# trackduino_mini.net
KiCad netlist of a schematic drawn in EAGLE
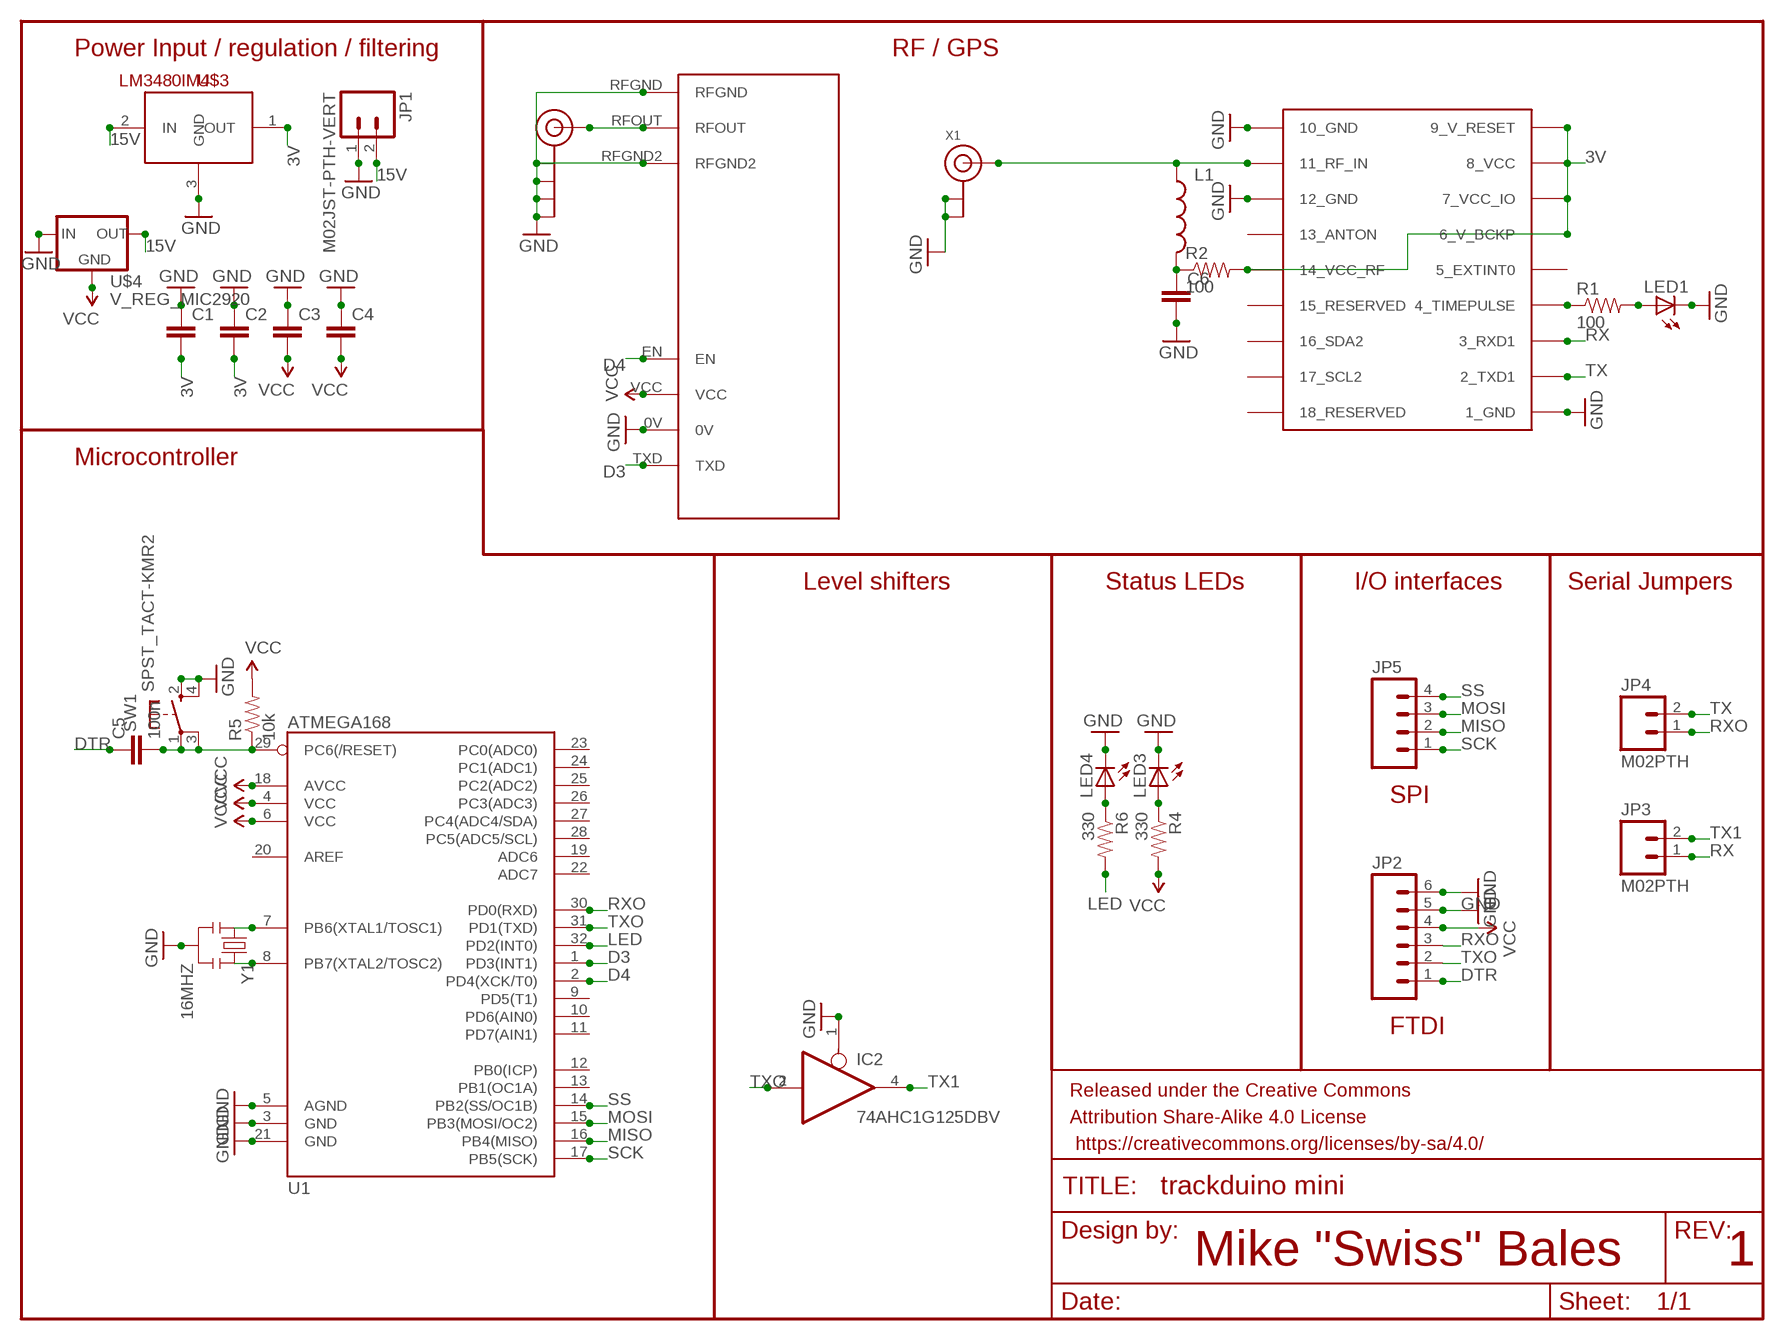
[diagram p0: schematic, sheet 1]

(export (version "E")
  (design (tool "Eeschema 10.0.6"))
  (components
    (comp (ref "C1")
      (value "CAP0805")
      (footprint "eagle-import:0805")
      (libsource (lib "eagle-import") (part "CAP0805"))
    )
    (comp (ref "C2")
      (value "CAP0805")
      (footprint "eagle-import:0805")
      (libsource (lib "eagle-import") (part "CAP0805"))
    )
    (comp (ref "C3")
      (value "CAP0805")
      (footprint "eagle-import:0805")
      (libsource (lib "eagle-import") (part "CAP0805"))
    )
    (comp (ref "C4")
      (value "CAP0805")
      (footprint "eagle-import:0805")
      (libsource (lib "eagle-import") (part "CAP0805"))
    )
    (comp (ref "C5")
      (value "100n")
      (footprint "eagle-import:0805")
      (libsource (lib "eagle-import") (part "CAP0805"))
    )
    (comp (ref "C6")
      (value "CAP0805")
      (footprint "eagle-import:0805")
      (libsource (lib "eagle-import") (part "CAP0805"))
    )
    (comp (ref "FRAME1")
      (value "FRAME-LETTER")
      (footprint "eagle-import:CREATIVE_COMMONS")
      (libsource (lib "eagle-import") (part "FRAME-LETTER"))
    )
    (comp (ref "IC2")
      (value "74AHC1G125DBV")
      (footprint "eagle-import:SOT23-5")
      (libsource (lib "eagle-import") (part "741G125DBVAHC"))
    )
    (comp (ref "J$1")
      (value "SMA_EDGE")
      (footprint "eagle-import:SMA-EDGE")
      (libsource (lib "eagle-import") (part "SMA_EDGE"))
    )
    (comp (ref "JP1")
      (value "M02JST-PTH-VERT")
      (footprint "eagle-import:JST-2-PTH-VERT")
      (libsource (lib "eagle-import") (part "M02JST-PTH-VERT"))
    )
    (comp (ref "JP2")
      (value "M06NO_SILK_FEMALE_PTH")
      (footprint "eagle-import:1X06_NO_SILK")
      (libsource (lib "eagle-import") (part "M06NO_SILK_FEMALE_PTH"))
    )
    (comp (ref "JP3")
      (value "M02PTH")
      (footprint "eagle-import:1X02")
      (libsource (lib "eagle-import") (part "M02PTH"))
    )
    (comp (ref "JP4")
      (value "M02PTH")
      (footprint "eagle-import:1X02")
      (libsource (lib "eagle-import") (part "M02PTH"))
    )
    (comp (ref "JP5")
      (value "M041X04_NO_SILK")
      (footprint "eagle-import:1X04_NO_SILK")
      (libsource (lib "eagle-import") (part "M041X04_NO_SILK"))
    )
    (comp (ref "L1")
      (value "INDUCTOR0805")
      (footprint "eagle-import:0805")
      (libsource (lib "eagle-import") (part "INDUCTOR0805"))
    )
    (comp (ref "LED1")
      (value "LEDCHIP-LED0805")
      (footprint "eagle-import:CHIP-LED0805")
      (libsource (lib "eagle-import") (part "LEDCHIP-LED0805"))
    )
    (comp (ref "LED3")
      (value "LEDCHIP-LED0805")
      (footprint "eagle-import:CHIP-LED0805")
      (libsource (lib "eagle-import") (part "LEDCHIP-LED0805"))
    )
    (comp (ref "LED4")
      (value "LEDCHIP-LED0805")
      (footprint "eagle-import:CHIP-LED0805")
      (libsource (lib "eagle-import") (part "LEDCHIP-LED0805"))
    )
    (comp (ref "R1")
      (value "100")
      (footprint "eagle-import:0805")
      (libsource (lib "eagle-import") (part "RESISTOR0805-RES"))
    )
    (comp (ref "R2")
      (value "100")
      (footprint "eagle-import:0805")
      (libsource (lib "eagle-import") (part "RESISTOR0805-RES"))
    )
    (comp (ref "R4")
      (value "330")
      (footprint "eagle-import:0805")
      (libsource (lib "eagle-import") (part "RESISTOR0805-RES"))
    )
    (comp (ref "R5")
      (value "10k")
      (footprint "eagle-import:0805")
      (libsource (lib "eagle-import") (part "RESISTOR0805-RES"))
    )
    (comp (ref "R6")
      (value "330")
      (footprint "eagle-import:0805")
      (libsource (lib "eagle-import") (part "RESISTOR0805-RES"))
    )
    (comp (ref "SW1")
      (value "SPST_TACT-KMR2")
      (footprint "eagle-import:KMR2")
      (libsource (lib "eagle-import") (part "SPST_TACT-KMR2"))
    )
    (comp (ref "U$1")
      (value "UBLOX_MAX")
      (footprint "eagle-import:UBLOX_MAX")
      (libsource (lib "eagle-import") (part "UBLOX_MAX"))
    )
    (comp (ref "U$2")
      (value "RADIOMETRIX-HX1")
      (footprint "eagle-import:RADIOMETRIX-HX1")
      (libsource (lib "eagle-import") (part "RADIOMETRIX-HX1"))
    )
    (comp (ref "U$3")
      (value "LM3480IM4")
      (footprint "eagle-import:SOT23-3")
      (libsource (lib "eagle-import") (part "LM3480IM4"))
    )
    (comp (ref "U$4")
      (value "V_REG_MIC2920")
      (footprint "eagle-import:SOT223")
      (libsource (lib "eagle-import") (part "V_REG_MIC2920"))
    )
    (comp (ref "U1")
      (value "ATMEGA168")
      (footprint "eagle-import:TQFP32-08")
      (libsource (lib "eagle-import") (part "ATMEGA168"))
    )
    (comp (ref "X1")
      (value "ANTENNA_U.FL")
      (footprint "eagle-import:U.FL")
      (libsource (lib "eagle-import") (part "ANTENNA_U.FL"))
    )
    (comp (ref "Y1")
      (value "16MHZ")
      (footprint "eagle-import:RESONATOR-SMD")
      (libsource (lib "eagle-import") (part "RESONATOR16MHZ"))
    )
  )
  (nets
    (net (code "1") (name "/3V") (class "Default")
      (node (ref "C1") (pin "2") (pinfunction "2_2") (pintype "passive"))
      (node (ref "C2") (pin "2") (pinfunction "2_2") (pintype "passive"))
      (node (ref "R2") (pin "2") (pinfunction "2_2") (pintype "passive"))
      (node (ref "U$1") (pin "14_VCC_RF") (pinfunction "14_VCC_RF_14_VCC_RF") (pintype "bidirectional"))
      (node (ref "U$1") (pin "6_V_BCKP") (pinfunction "6_V_BCKP_6_V_BCKP") (pintype "bidirectional"))
      (node (ref "U$1") (pin "7_VCC_IO") (pinfunction "7_VCC_IO_7_VCC_IO") (pintype "power_in"))
      (node (ref "U$1") (pin "8_VCC") (pinfunction "8_VCC_8_VCC") (pintype "power_in"))
      (node (ref "U$1") (pin "9_V_RESET") (pinfunction "9_V_RESET_9_V_RESET") (pintype "power_in"))
      (node (ref "U$3") (pin "1") (pinfunction "OUT_1") (pintype "bidirectional"))
    )
    (net (code "2") (name "/15V") (class "Default")
      (node (ref "JP1") (pin "2") (pinfunction "2_2") (pintype "passive"))
      (node (ref "U$3") (pin "2") (pinfunction "IN_2") (pintype "bidirectional"))
      (node (ref "U$4") (pin "3") (pinfunction "OUT_3") (pintype "output"))
    )
    (net (code "3") (name "/D3") (class "Default")
      (node (ref "U$2") (pin "TXD") (pinfunction "TXD_TXD") (pintype "bidirectional"))
      (node (ref "U1") (pin "1") (pinfunction "PD3(INT1)_1") (pintype "bidirectional"))
    )
    (net (code "4") (name "/D4") (class "Default")
      (node (ref "U$2") (pin "EN") (pinfunction "EN_EN") (pintype "bidirectional"))
      (node (ref "U1") (pin "2") (pinfunction "PD4(XCK/T0)_2") (pintype "bidirectional"))
    )
    (net (code "5") (name "/DTR") (class "Default")
      (node (ref "C5") (pin "1") (pinfunction "1_1") (pintype "passive"))
      (node (ref "JP2") (pin "1") (pinfunction "1_1") (pintype "passive"))
    )
    (net (code "6") (name "/LED") (class "Default")
      (node (ref "R6") (pin "2") (pinfunction "2_2") (pintype "passive"))
      (node (ref "U1") (pin "32") (pinfunction "PD2(INT0)_32") (pintype "bidirectional"))
    )
    (net (code "7") (name "/MISO") (class "Default")
      (node (ref "JP5") (pin "2") (pinfunction "2_2") (pintype "passive"))
      (node (ref "U1") (pin "16") (pinfunction "PB4(MISO)_16") (pintype "bidirectional"))
    )
    (net (code "8") (name "/MOSI") (class "Default")
      (node (ref "JP5") (pin "3") (pinfunction "3_3") (pintype "passive"))
      (node (ref "U1") (pin "15") (pinfunction "PB3(MOSI/OC2)_15") (pintype "bidirectional"))
    )
    (net (code "9") (name "/RX") (class "Default")
      (node (ref "JP3") (pin "1") (pinfunction "1_1") (pintype "passive"))
      (node (ref "U$1") (pin "3_RXD1") (pinfunction "3_RXD1_3_RXD1") (pintype "bidirectional"))
    )
    (net (code "10") (name "/RXO") (class "Default")
      (node (ref "JP2") (pin "3") (pinfunction "3_3") (pintype "passive"))
      (node (ref "JP4") (pin "1") (pinfunction "1_1") (pintype "passive"))
      (node (ref "U1") (pin "30") (pinfunction "PD0(RXD)_30") (pintype "bidirectional"))
    )
    (net (code "11") (name "/SCK") (class "Default")
      (node (ref "JP5") (pin "1") (pinfunction "1_1") (pintype "passive"))
      (node (ref "U1") (pin "17") (pinfunction "PB5(SCK)_17") (pintype "bidirectional"))
    )
    (net (code "12") (name "/SS") (class "Default")
      (node (ref "JP5") (pin "4") (pinfunction "4_4") (pintype "passive"))
      (node (ref "U1") (pin "14") (pinfunction "PB2(SS/OC1B)_14") (pintype "bidirectional"))
    )
    (net (code "13") (name "/TX") (class "Default")
      (node (ref "JP4") (pin "2") (pinfunction "2_2") (pintype "passive"))
      (node (ref "U$1") (pin "2_TXD1") (pinfunction "2_TXD1_2_TXD1") (pintype "bidirectional"))
    )
    (net (code "14") (name "/TX1") (class "Default")
      (node (ref "IC2") (pin "4") (pinfunction "O_4") (pintype "tri_state"))
      (node (ref "JP3") (pin "2") (pinfunction "2_2") (pintype "passive"))
    )
    (net (code "15") (name "/TXO") (class "Default")
      (node (ref "IC2") (pin "2") (pinfunction "I_2") (pintype "input"))
      (node (ref "JP2") (pin "2") (pinfunction "2_2") (pintype "passive"))
      (node (ref "U1") (pin "31") (pinfunction "PD1(TXD)_31") (pintype "bidirectional"))
    )
    (net (code "16") (name "GND") (class "Default")
      (node (ref "C1") (pin "1") (pinfunction "1_1") (pintype "passive"))
      (node (ref "C2") (pin "1") (pinfunction "1_1") (pintype "passive"))
      (node (ref "C3") (pin "1") (pinfunction "1_1") (pintype "passive"))
      (node (ref "C4") (pin "1") (pinfunction "1_1") (pintype "passive"))
      (node (ref "C6") (pin "2") (pinfunction "2_2") (pintype "passive"))
      (node (ref "IC2") (pin "1") (pinfunction "OE_1") (pintype "input"))
      (node (ref "J$1") (pin "GND@0") (pinfunction "GND_GND@0") (pintype "bidirectional"))
      (node (ref "J$1") (pin "GND@1") (pinfunction "GND_GND@1") (pintype "bidirectional"))
      (node (ref "J$1") (pin "GND@2") (pinfunction "GND_GND@2") (pintype "bidirectional"))
      (node (ref "J$1") (pin "GND@3") (pinfunction "GND_GND@3") (pintype "bidirectional"))
      (node (ref "JP1") (pin "1") (pinfunction "1_1") (pintype "passive"))
      (node (ref "JP2") (pin "5") (pinfunction "5_5") (pintype "passive"))
      (node (ref "JP2") (pin "6") (pinfunction "6_6") (pintype "passive"))
      (node (ref "LED1") (pin "C") (pinfunction "C_C") (pintype "passive"))
      (node (ref "LED3") (pin "C") (pinfunction "C_C") (pintype "passive"))
      (node (ref "LED4") (pin "C") (pinfunction "C_C") (pintype "passive"))
      (node (ref "SW1") (pin "2") (pinfunction "S_2") (pintype "passive"))
      (node (ref "SW1") (pin "4") (pinfunction "S1_4") (pintype "passive"))
      (node (ref "U$1") (pin "10_GND") (pinfunction "10_GND_10_GND") (pintype "power_in"))
      (node (ref "U$1") (pin "12_GND") (pinfunction "12_GND_12_GND") (pintype "power_in"))
      (node (ref "U$1") (pin "1_GND") (pinfunction "1_GND_1_GND") (pintype "power_in"))
      (node (ref "U$2") (pin "0V") (pinfunction "0V_0V") (pintype "bidirectional"))
      (node (ref "U$2") (pin "RFGND") (pinfunction "RFGND_RFGND") (pintype "bidirectional"))
      (node (ref "U$2") (pin "RFGND2") (pinfunction "RFGND2_RFGND2") (pintype "bidirectional"))
      (node (ref "U$3") (pin "3") (pinfunction "GND_3") (pintype "bidirectional"))
      (node (ref "U$4") (pin "1") (pinfunction "IN_1") (pintype "input"))
      (node (ref "U1") (pin "21") (pinfunction "GND_21") (pintype "bidirectional"))
      (node (ref "U1") (pin "3") (pinfunction "GND_3") (pintype "bidirectional"))
      (node (ref "U1") (pin "5") (pinfunction "AGND_5") (pintype "bidirectional"))
      (node (ref "X1") (pin "1") (pinfunction "GND_1") (pintype "passive"))
      (node (ref "X1") (pin "2") (pinfunction "GND_2") (pintype "passive"))
      (node (ref "Y1") (pin "2") (pinfunction "2_2") (pintype "passive"))
    )
    (net (code "17") (name "Net-(C6-Pad1)") (class "Default")
      (node (ref "C6") (pin "1") (pinfunction "1_1") (pintype "passive"))
      (node (ref "L1") (pin "2") (pinfunction "2_2") (pintype "passive"))
      (node (ref "R2") (pin "1") (pinfunction "1_1") (pintype "passive"))
    )
    (net (code "18") (name "Net-(J$1-SIGNAL)") (class "Default")
      (node (ref "J$1") (pin "SIG") (pinfunction "SIGNAL_SIG") (pintype "bidirectional"))
      (node (ref "U$2") (pin "RFOUT") (pinfunction "RFOUT_RFOUT") (pintype "bidirectional"))
    )
    (net (code "19") (name "Net-(LED1-PadA)") (class "Default")
      (node (ref "LED1") (pin "A") (pinfunction "A_A") (pintype "passive"))
      (node (ref "R1") (pin "2") (pinfunction "2_2") (pintype "passive"))
    )
    (net (code "20") (name "Net-(LED3-PadA)") (class "Default")
      (node (ref "LED3") (pin "A") (pinfunction "A_A") (pintype "passive"))
      (node (ref "R4") (pin "1") (pinfunction "1_1") (pintype "passive"))
    )
    (net (code "21") (name "Net-(LED4-PadA)") (class "Default")
      (node (ref "LED4") (pin "A") (pinfunction "A_A") (pintype "passive"))
      (node (ref "R6") (pin "1") (pinfunction "1_1") (pintype "passive"))
    )
    (net (code "22") (name "Net-(R1-Pad1)") (class "Default")
      (node (ref "R1") (pin "1") (pinfunction "1_1") (pintype "passive"))
      (node (ref "U$1") (pin "4_TIMEPULSE") (pinfunction "4_TIMEPULSE_4_TIMEPULSE") (pintype "bidirectional"))
    )
    (net (code "23") (name "Net-(SW1-P)") (class "Default")
      (node (ref "C5") (pin "2") (pinfunction "2_2") (pintype "passive"))
      (node (ref "R5") (pin "1") (pinfunction "1_1") (pintype "passive"))
      (node (ref "SW1") (pin "1") (pinfunction "P_1") (pintype "passive"))
      (node (ref "SW1") (pin "3") (pinfunction "P1_3") (pintype "passive"))
      (node (ref "U1") (pin "29") (pinfunction "PC6(/RESET)_29") (pintype "bidirectional"))
    )
    (net (code "24") (name "Net-(U1-PB6(XTAL1{slash}TOSC1))") (class "Default")
      (node (ref "U1") (pin "7") (pinfunction "PB6(XTAL1/TOSC1)_7") (pintype "bidirectional"))
      (node (ref "Y1") (pin "1") (pinfunction "1_1") (pintype "passive"))
    )
    (net (code "25") (name "Net-(U1-PB7(XTAL2{slash}TOSC2))") (class "Default")
      (node (ref "U1") (pin "8") (pinfunction "PB7(XTAL2/TOSC2)_8") (pintype "bidirectional"))
      (node (ref "Y1") (pin "3") (pinfunction "3_3") (pintype "passive"))
    )
    (net (code "26") (name "Net-(X1-SIGNAL)") (class "Default")
      (node (ref "L1") (pin "1") (pinfunction "1_1") (pintype "passive"))
      (node (ref "U$1") (pin "11_RF_IN") (pinfunction "11_RF_IN_11_RF_IN") (pintype "bidirectional"))
      (node (ref "X1") (pin "3") (pinfunction "SIGNAL_3") (pintype "passive"))
    )
    (net (code "27") (name "VCC") (class "Default")
      (node (ref "C3") (pin "2") (pinfunction "2_2") (pintype "passive"))
      (node (ref "C4") (pin "2") (pinfunction "2_2") (pintype "passive"))
      (node (ref "JP2") (pin "4") (pinfunction "4_4") (pintype "passive"))
      (node (ref "R4") (pin "2") (pinfunction "2_2") (pintype "passive"))
      (node (ref "R5") (pin "2") (pinfunction "2_2") (pintype "passive"))
      (node (ref "U$2") (pin "VCC") (pinfunction "VCC_VCC") (pintype "bidirectional"))
      (node (ref "U$4") (pin "2") (pinfunction "GND_2") (pintype "input"))
      (node (ref "U1") (pin "18") (pinfunction "AVCC_18") (pintype "bidirectional"))
      (node (ref "U1") (pin "4") (pinfunction "VCC_4") (pintype "bidirectional"))
      (node (ref "U1") (pin "6") (pinfunction "VCC_6") (pintype "bidirectional"))
    )
    (net (code "28") (name "unconnected-(U$1-Pad5_EXTINT0)") (class "Default")
      (node (ref "U$1") (pin "5_EXTINT0") (pinfunction "5_EXTINT0_5_EXTINT0") (pintype "bidirectional"))
    )
    (net (code "29") (name "unconnected-(U$1-Pad13_ANTON)") (class "Default")
      (node (ref "U$1") (pin "13_ANTON") (pinfunction "13_ANTON_13_ANTON") (pintype "bidirectional"))
    )
    (net (code "30") (name "unconnected-(U$1-Pad15_RESERVED)") (class "Default")
      (node (ref "U$1") (pin "15_RESERVED") (pinfunction "15_RESERVED_15_RESERVED") (pintype "bidirectional"))
    )
    (net (code "31") (name "unconnected-(U$1-Pad16_SDA2)") (class "Default")
      (node (ref "U$1") (pin "16_SDA2") (pinfunction "16_SDA2_16_SDA2") (pintype "bidirectional"))
    )
    (net (code "32") (name "unconnected-(U$1-Pad17_SCL2)") (class "Default")
      (node (ref "U$1") (pin "17_SCL2") (pinfunction "17_SCL2_17_SCL2") (pintype "bidirectional"))
    )
    (net (code "33") (name "unconnected-(U$1-Pad18_RESERVED)") (class "Default")
      (node (ref "U$1") (pin "18_RESERVED") (pinfunction "18_RESERVED_18_RESERVED") (pintype "bidirectional"))
    )
    (net (code "34") (name "unconnected-(U1-ADC6-Pad19)") (class "Default")
      (node (ref "U1") (pin "19") (pinfunction "ADC6_19") (pintype "bidirectional"))
    )
    (net (code "35") (name "unconnected-(U1-ADC7-Pad22)") (class "Default")
      (node (ref "U1") (pin "22") (pinfunction "ADC7_22") (pintype "bidirectional"))
    )
    (net (code "36") (name "unconnected-(U1-AREF-Pad20)") (class "Default")
      (node (ref "U1") (pin "20") (pinfunction "AREF_20") (pintype "bidirectional"))
    )
    (net (code "37") (name "unconnected-(U1-PB0(ICP)-Pad12)") (class "Default")
      (node (ref "U1") (pin "12") (pinfunction "PB0(ICP)_12") (pintype "bidirectional"))
    )
    (net (code "38") (name "unconnected-(U1-PB1(OC1A)-Pad13)") (class "Default")
      (node (ref "U1") (pin "13") (pinfunction "PB1(OC1A)_13") (pintype "bidirectional"))
    )
    (net (code "39") (name "unconnected-(U1-PC0(ADC0)-Pad23)") (class "Default")
      (node (ref "U1") (pin "23") (pinfunction "PC0(ADC0)_23") (pintype "bidirectional"))
    )
    (net (code "40") (name "unconnected-(U1-PC1(ADC1)-Pad24)") (class "Default")
      (node (ref "U1") (pin "24") (pinfunction "PC1(ADC1)_24") (pintype "bidirectional"))
    )
    (net (code "41") (name "unconnected-(U1-PC2(ADC2)-Pad25)") (class "Default")
      (node (ref "U1") (pin "25") (pinfunction "PC2(ADC2)_25") (pintype "bidirectional"))
    )
    (net (code "42") (name "unconnected-(U1-PC3(ADC3)-Pad26)") (class "Default")
      (node (ref "U1") (pin "26") (pinfunction "PC3(ADC3)_26") (pintype "bidirectional"))
    )
    (net (code "43") (name "unconnected-(U1-PC4(ADC4{slash}SDA)-Pad27)") (class "Default")
      (node (ref "U1") (pin "27") (pinfunction "PC4(ADC4/SDA)_27") (pintype "bidirectional"))
    )
    (net (code "44") (name "unconnected-(U1-PC5(ADC5{slash}SCL)-Pad28)") (class "Default")
      (node (ref "U1") (pin "28") (pinfunction "PC5(ADC5/SCL)_28") (pintype "bidirectional"))
    )
    (net (code "45") (name "unconnected-(U1-PD5(T1)-Pad9)") (class "Default")
      (node (ref "U1") (pin "9") (pinfunction "PD5(T1)_9") (pintype "bidirectional"))
    )
    (net (code "46") (name "unconnected-(U1-PD6(AIN0)-Pad10)") (class "Default")
      (node (ref "U1") (pin "10") (pinfunction "PD6(AIN0)_10") (pintype "bidirectional"))
    )
    (net (code "47") (name "unconnected-(U1-PD7(AIN1)-Pad11)") (class "Default")
      (node (ref "U1") (pin "11") (pinfunction "PD7(AIN1)_11") (pintype "bidirectional"))
    )
  )
)
